# STM32L441CE_4L-2-Copy.net
KiCad netlist of a schematic drawn in EAGLE
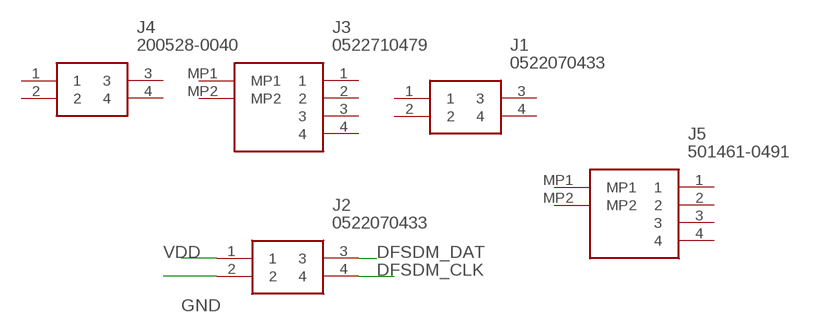
[diagram p0: schematic, sheet 1]
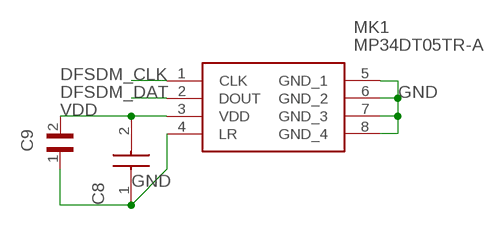
[diagram p1: schematic, sheet 2]

(export (version "E")
  (design (tool "Eeschema 10.0.6"))
  (components
    (comp (ref "C8")
      (value "AMK063AC6105KP-F")
      (footprint "eagle-import:CAPC0603X33N")
      (fields (field (name "MOUSER_PART_NUMBER") "963-AMK063AC6105KP-F"))
      (libsource (lib "eagle-import") (part "AMK063AC6105KP-F"))
    )
    (comp (ref "C9")
      (value "GRM033C80J104KE15D")
      (footprint "eagle-import:CAPC0603X33N")
      (fields (field (name "DIGI-KEY_PART_NUMBER") "490-10390-1-ND") (field (name "MF") "Murata Electronics"))
      (libsource (lib "eagle-import") (part "GRM033C80J104KE15D"))
    )
    (comp (ref "MK1")
      (value "MP34DT05TR-A")
      (footprint "eagle-import:MP34DT05TRA")
      (fields (field (name "MOUSER_PART_NUMBER") "511-MP34DT05TR-A"))
      (libsource (lib "eagle-import") (part "MP34DT05TR-A"))
    )
    (comp (ref "J1")
      (value "0522070433")
      (footprint "eagle-import:0522070433")
      (libsource (lib "eagle-import") (part "0522070433"))
    )
    (comp (ref "J2")
      (value "0522070433")
      (footprint "eagle-import:0522070433")
      (libsource (lib "eagle-import") (part "0522070433_1_0522070433"))
    )
    (comp (ref "J3")
      (value "0522710479")
      (footprint "eagle-import:0522710479")
      (libsource (lib "eagle-import") (part "0522710479"))
    )
    (comp (ref "J4")
      (value "200528-0040")
      (footprint "eagle-import:200528-0040")
      (fields (field (name "MOUSER_PART_NUMBER") "538-200528-0040"))
      (libsource (lib "eagle-import") (part "200528-0040"))
    )
    (comp (ref "J5")
      (value "501461-0491")
      (footprint "eagle-import:5014610491")
      (fields (field (name "MOUSER_PART_NUMBER") "538-501461-0491"))
      (libsource (lib "eagle-import") (part "501461-0491"))
    )
  )
  (nets
    (net (code "1") (name "DFSDM_CLK") (class "Default")
      (node (ref "J2") (pin "4") (pinfunction "4_4") (pintype "bidirectional"))
      (node (ref "MK1") (pin "1") (pinfunction "CLK_1") (pintype "bidirectional"))
    )
    (net (code "2") (name "DFSDM_DAT") (class "Default")
      (node (ref "J2") (pin "3") (pinfunction "3_3") (pintype "bidirectional"))
      (node (ref "MK1") (pin "2") (pinfunction "DOUT_2") (pintype "bidirectional"))
    )
    (net (code "3") (name "GND") (class "Default")
      (node (ref "C8") (pin "1") (pinfunction "1_1") (pintype "bidirectional"))
      (node (ref "C9") (pin "1") (pinfunction "1_1") (pintype "passive"))
      (node (ref "J2") (pin "2") (pinfunction "2_2") (pintype "bidirectional"))
      (node (ref "MK1") (pin "4") (pinfunction "LR_4") (pintype "bidirectional"))
      (node (ref "MK1") (pin "5") (pinfunction "GND_1_5") (pintype "bidirectional"))
      (node (ref "MK1") (pin "6") (pinfunction "GND_2_6") (pintype "bidirectional"))
      (node (ref "MK1") (pin "7") (pinfunction "GND_3_7") (pintype "bidirectional"))
      (node (ref "MK1") (pin "8") (pinfunction "GND_4_8") (pintype "bidirectional"))
    )
    (net (code "4") (name "VDD") (class "Default")
      (node (ref "C8") (pin "2") (pinfunction "2_2") (pintype "bidirectional"))
      (node (ref "C9") (pin "2") (pinfunction "2_2") (pintype "passive"))
      (node (ref "J2") (pin "1") (pinfunction "1_1") (pintype "bidirectional"))
      (node (ref "MK1") (pin "3") (pinfunction "VDD_3") (pintype "bidirectional"))
    )
    (net (code "5") (name "unconnected-(J1-Pad1)") (class "Default")
      (node (ref "J1") (pin "1") (pinfunction "1_1") (pintype "bidirectional"))
    )
    (net (code "6") (name "unconnected-(J1-Pad2)") (class "Default")
      (node (ref "J1") (pin "2") (pinfunction "2_2") (pintype "bidirectional"))
    )
    (net (code "7") (name "unconnected-(J1-Pad3)") (class "Default")
      (node (ref "J1") (pin "3") (pinfunction "3_3") (pintype "bidirectional"))
    )
    (net (code "8") (name "unconnected-(J1-Pad4)") (class "Default")
      (node (ref "J1") (pin "4") (pinfunction "4_4") (pintype "bidirectional"))
    )
    (net (code "9") (name "unconnected-(J3-Pad1)") (class "Default")
      (node (ref "J3") (pin "1") (pinfunction "1_1") (pintype "bidirectional"))
    )
    (net (code "10") (name "unconnected-(J3-Pad2)") (class "Default")
      (node (ref "J3") (pin "2") (pinfunction "2_2") (pintype "bidirectional"))
    )
    (net (code "11") (name "unconnected-(J3-Pad3)") (class "Default")
      (node (ref "J3") (pin "3") (pinfunction "3_3") (pintype "bidirectional"))
    )
    (net (code "12") (name "unconnected-(J3-Pad4)") (class "Default")
      (node (ref "J3") (pin "4") (pinfunction "4_4") (pintype "bidirectional"))
    )
    (net (code "13") (name "unconnected-(J3-PadMP1)") (class "Default")
      (node (ref "J3") (pin "MP1") (pinfunction "MP1_MP1") (pintype "bidirectional"))
    )
    (net (code "14") (name "unconnected-(J3-PadMP2)") (class "Default")
      (node (ref "J3") (pin "MP2") (pinfunction "MP2_MP2") (pintype "bidirectional"))
    )
    (net (code "15") (name "unconnected-(J4-Pad1)") (class "Default")
      (node (ref "J4") (pin "1") (pinfunction "1_1") (pintype "bidirectional"))
    )
    (net (code "16") (name "unconnected-(J4-Pad2)") (class "Default")
      (node (ref "J4") (pin "2") (pinfunction "2_2") (pintype "bidirectional"))
    )
    (net (code "17") (name "unconnected-(J4-Pad3)") (class "Default")
      (node (ref "J4") (pin "3") (pinfunction "3_3") (pintype "bidirectional"))
    )
    (net (code "18") (name "unconnected-(J4-Pad4)") (class "Default")
      (node (ref "J4") (pin "4") (pinfunction "4_4") (pintype "bidirectional"))
    )
    (net (code "19") (name "unconnected-(J5-Pad1)") (class "Default")
      (node (ref "J5") (pin "1") (pinfunction "1_1") (pintype "bidirectional"))
    )
    (net (code "20") (name "unconnected-(J5-Pad2)") (class "Default")
      (node (ref "J5") (pin "2") (pinfunction "2_2") (pintype "bidirectional"))
    )
    (net (code "21") (name "unconnected-(J5-Pad3)") (class "Default")
      (node (ref "J5") (pin "3") (pinfunction "3_3") (pintype "bidirectional"))
    )
    (net (code "22") (name "unconnected-(J5-Pad4)") (class "Default")
      (node (ref "J5") (pin "4") (pinfunction "4_4") (pintype "bidirectional"))
    )
    (net (code "23") (name "unconnected-(J5-PadMP1)") (class "Default")
      (node (ref "J5") (pin "MP1") (pinfunction "MP1_MP1") (pintype "bidirectional"))
    )
    (net (code "24") (name "unconnected-(J5-PadMP2)") (class "Default")
      (node (ref "J5") (pin "MP2") (pinfunction "MP2_MP2") (pintype "bidirectional"))
    )
  )
)
